# BidirectionalSwitch.net
KiCad netlist of a schematic drawn in Altium Designer
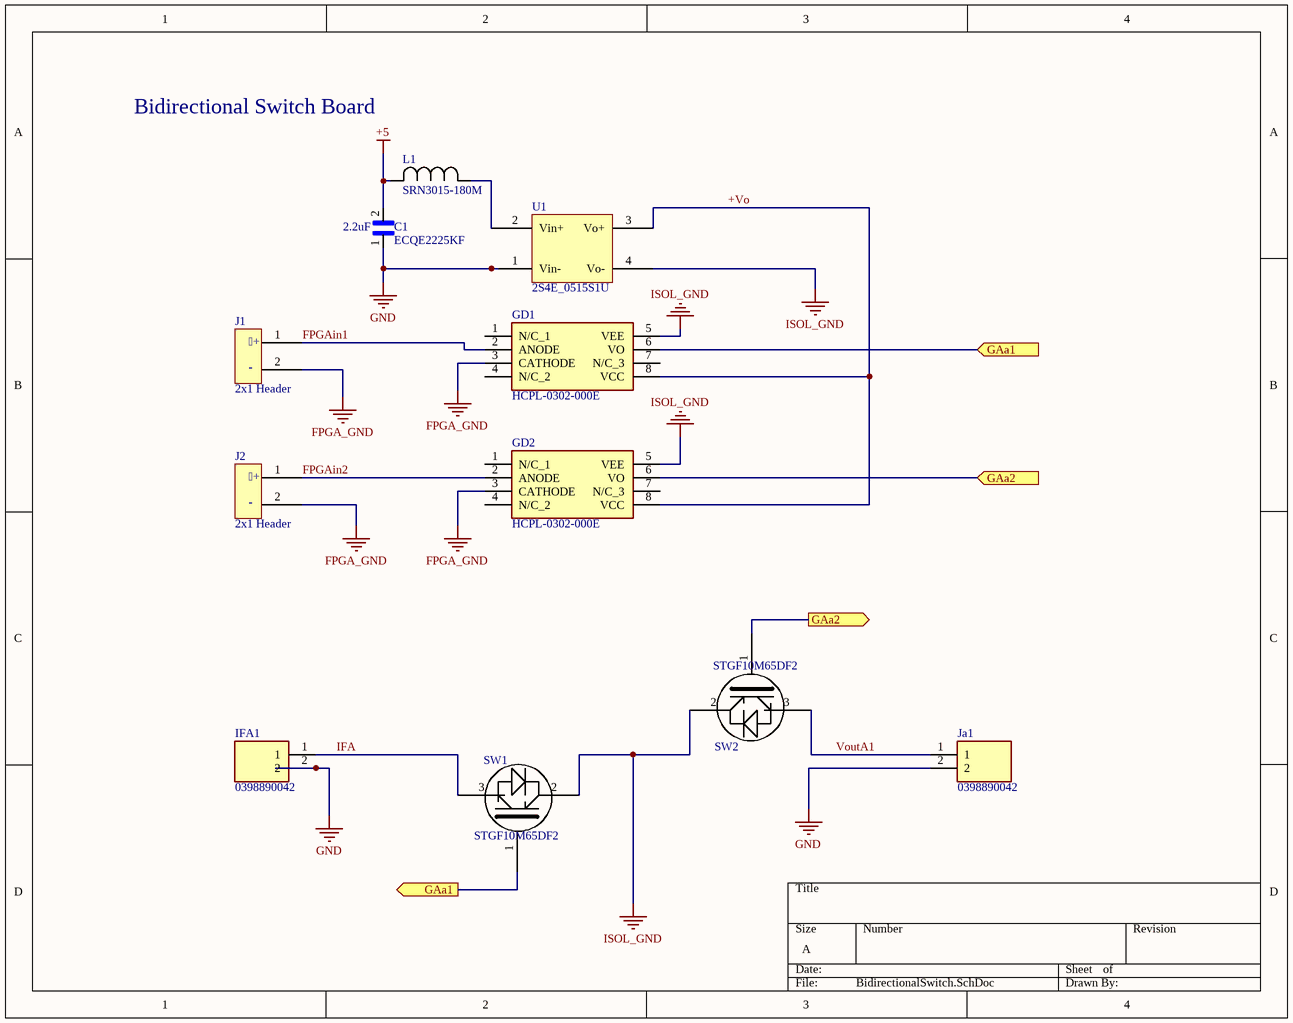
[diagram p0: BidirectionalSwitch.SchDoc]

(export (version "E")
  (design (tool "Eeschema 10.0.6"))
  (components
    (comp (ref "C1")
      (value "ECQE2225KF")
      (footprint "CAPRR2250W80L2600T850H1630")
      (fields (field (name "ALTIUM_VALUE") "2.2uF"))
      (libsource (lib "ECQE2225KF") (part "ECQE2225KF"))
    )
    (comp (ref "GD1")
      (value "HCPL-0302-000E")
      (footprint "SamacSys:SOT127P599X361-8N")
      (description "Integrated Circuit")
      (fields (field (name "MOUSER PART NUMBER") "630-HCPL-0302-000E"))
      (libsource (lib "SamacSys") (part "HCPL-0302-000E"))
    )
    (comp (ref "GD2")
      (value "HCPL-0302-000E")
      (footprint "SamacSys:SOT127P599X361-8N")
      (description "Integrated Circuit")
      (fields (field (name "MOUSER PART NUMBER") "630-HCPL-0302-000E"))
      (libsource (lib "*") (part "HCPL-0302-000E"))
    )
    (comp (ref "IFA1")
      (value "0398890042")
      (footprint "0398890042")
      (description "Conn Eurostyle Block 2 POS 5.08mm Solder ST Thru-Hole 17.5A/Contact")
      (libsource (lib "0398890042") (part "0398890042"))
    )
    (comp (ref "J1") (value "1") (libsource (lib "Header2x1") (part "Header 2x1")))
    (comp (ref "J2") (value "1") (libsource (lib "Header2x1") (part "Header 2x1")))
    (comp (ref "Ja1")
      (value "0398890042")
      (footprint "0398890042")
      (description "Conn Eurostyle Block 2 POS 5.08mm Solder ST Thru-Hole 17.5A/Contact")
      (libsource (lib "") (part "0398890042_1"))
    )
    (comp (ref "L1")
      (value "SRN3015-180M")
      (footprint "IND_BOURNS_SRN3015")
      (description "No Description Available")
      (libsource (lib "SRN3015-180M") (part "SRN3015-180M"))
    )
    (comp (ref "SW1")
      (value "STGF10M65DF2")
      (footprint "TO-220FP_STM")
      (description "No Description Available")
      (libsource (lib "STGF10M65DF2") (part "STGF10M65DF2"))
    )
    (comp (ref "SW2")
      (value "STGF10M65DF2")
      (footprint "TO-220FP_STM")
      (description "No Description Available")
      (libsource (lib "STGF10M65DF2") (part "STGF10M65DF2"))
    )
    (comp (ref "U1")
      (value "2S4E_0515S1U")
      (footprint "2S4E_0515S1U")
      (description "2S4E_0515S1U DC-DC Converter")
      (libsource (lib "2S4E_0515S1U") (part "2S4E_0515S1U"))
    )
  )
  (nets
    (net (code "1") (name "+5") (class "Default")
      (node (ref "C1") (pin "2") (pinfunction "2_2") (pintype "passive"))
      (node (ref "L1") (pin "2") (pinfunction "2_2") (pintype "passive"))
    )
    (net (code "2") (name "/+Vo") (class "Default")
      (node (ref "GD1") (pin "8") (pinfunction "VCC_8") (pintype "passive"))
      (node (ref "GD2") (pin "8") (pinfunction "VCC_8") (pintype "passive"))
      (node (ref "U1") (pin "3") (pinfunction "Vo+_3") (pintype "power_in"))
    )
    (net (code "3") (name "/FPGAin1") (class "Default")
      (node (ref "GD1") (pin "2") (pinfunction "ANODE_2") (pintype "passive"))
      (node (ref "J1") (pin "1") (pinfunction "1_1") (pintype "passive"))
    )
    (net (code "4") (name "/FPGAin2") (class "Default")
      (node (ref "GD2") (pin "2") (pinfunction "ANODE_2") (pintype "passive"))
      (node (ref "J2") (pin "1") (pinfunction "1_1") (pintype "passive"))
    )
    (net (code "5") (name "/GAa1") (class "Default")
      (node (ref "GD1") (pin "6") (pinfunction "VO_6") (pintype "passive"))
      (node (ref "SW1") (pin "1") (pinfunction "G_1") (pintype "passive"))
    )
    (net (code "6") (name "/GAa2") (class "Default")
      (node (ref "GD2") (pin "6") (pinfunction "VO_6") (pintype "passive"))
      (node (ref "SW2") (pin "1") (pinfunction "G_1") (pintype "passive"))
    )
    (net (code "7") (name "/IFA") (class "Default")
      (node (ref "IFA1") (pin "1") (pinfunction "1_1") (pintype "passive"))
      (node (ref "SW1") (pin "3") (pinfunction "E_3") (pintype "passive"))
    )
    (net (code "8") (name "/VoutA1") (class "Default")
      (node (ref "Ja1") (pin "1") (pinfunction "1_1") (pintype "passive"))
      (node (ref "SW2") (pin "3") (pinfunction "E_3") (pintype "passive"))
    )
    (net (code "9") (name "FPGA_GND") (class "Default")
      (node (ref "GD1") (pin "3") (pinfunction "CATHODE_3") (pintype "passive"))
      (node (ref "GD2") (pin "3") (pinfunction "CATHODE_3") (pintype "passive"))
      (node (ref "J1") (pin "2") (pinfunction "2_2") (pintype "passive"))
      (node (ref "J2") (pin "2") (pinfunction "2_2") (pintype "passive"))
    )
    (net (code "10") (name "GND") (class "Default")
      (node (ref "C1") (pin "1") (pinfunction "1_1") (pintype "passive"))
      (node (ref "IFA1") (pin "2") (pinfunction "2_2") (pintype "passive"))
      (node (ref "Ja1") (pin "2") (pinfunction "2_2") (pintype "passive"))
      (node (ref "U1") (pin "1") (pinfunction "Vin-_1") (pintype "power_in"))
    )
    (net (code "11") (name "ISOL_GND") (class "Default")
      (node (ref "GD1") (pin "5") (pinfunction "VEE_5") (pintype "passive"))
      (node (ref "GD2") (pin "5") (pinfunction "VEE_5") (pintype "passive"))
      (node (ref "SW1") (pin "2") (pinfunction "C_2") (pintype "passive"))
      (node (ref "SW2") (pin "2") (pinfunction "C_2") (pintype "passive"))
      (node (ref "U1") (pin "4") (pinfunction "Vo-_4") (pintype "power_in"))
    )
    (net (code "12") (name "Net-(U1-Vin+)") (class "Default")
      (node (ref "L1") (pin "1") (pinfunction "1_1") (pintype "passive"))
      (node (ref "U1") (pin "2") (pinfunction "Vin+_2") (pintype "power_in"))
    )
    (net (code "13") (name "unconnected-(GD1-N{slash}C_1-Pad1)") (class "Default")
      (node (ref "GD1") (pin "1") (pinfunction "N/C_1_1") (pintype "passive"))
    )
    (net (code "14") (name "unconnected-(GD1-N{slash}C_2-Pad4)") (class "Default")
      (node (ref "GD1") (pin "4") (pinfunction "N/C_2_4") (pintype "passive"))
    )
    (net (code "15") (name "unconnected-(GD1-N{slash}C_3-Pad7)") (class "Default")
      (node (ref "GD1") (pin "7") (pinfunction "N/C_3_7") (pintype "passive"))
    )
    (net (code "16") (name "unconnected-(GD2-N{slash}C_1-Pad1)") (class "Default")
      (node (ref "GD2") (pin "1") (pinfunction "N/C_1_1") (pintype "passive"))
    )
    (net (code "17") (name "unconnected-(GD2-N{slash}C_2-Pad4)") (class "Default")
      (node (ref "GD2") (pin "4") (pinfunction "N/C_2_4") (pintype "passive"))
    )
    (net (code "18") (name "unconnected-(GD2-N{slash}C_3-Pad7)") (class "Default")
      (node (ref "GD2") (pin "7") (pinfunction "N/C_3_7") (pintype "passive"))
    )
  )
)
